# zeta2rework_lw_v20_wo_transistor.net
KiCad netlist of a schematic drawn in EAGLE
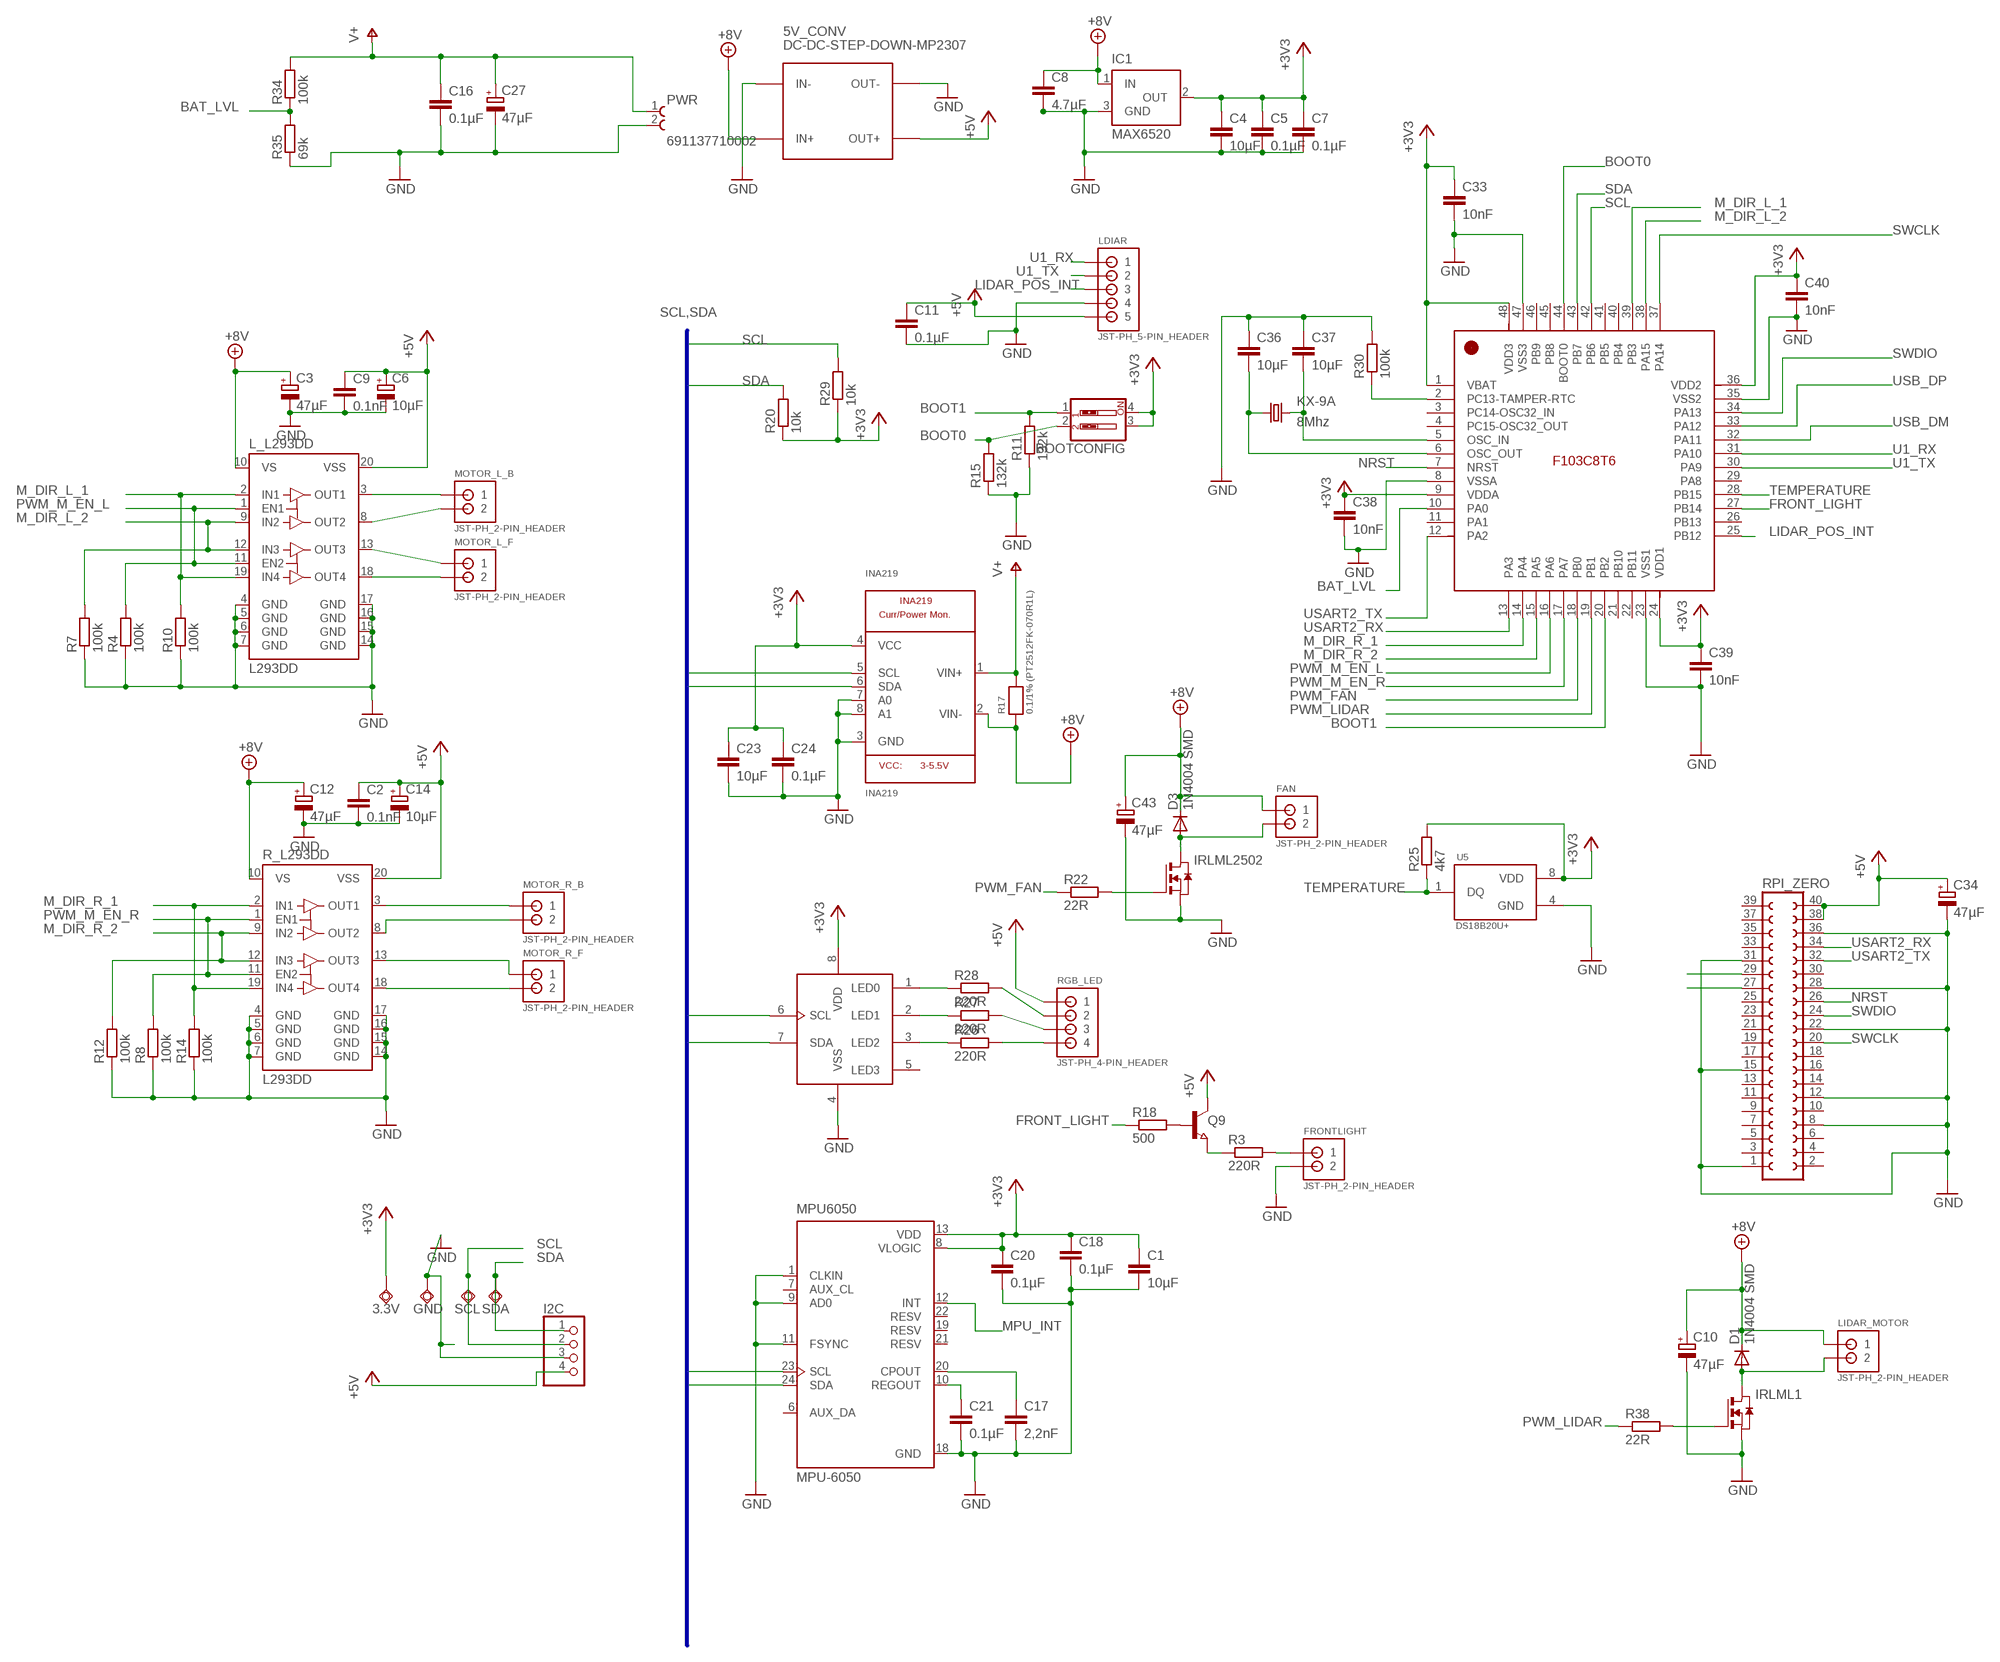
[diagram p0: schematic, sheet 1]

(export (version "E")
  (design (tool "Eeschema 10.0.6"))
  (components
    (comp (ref "3.3V")
      (value "TPSQTP20R")
      (footprint "eagle-import:TP20R")
      (libsource (lib "eagle-import") (part "TPSQTP20R"))
    )
    (comp (ref "5V_CONV")
      (value "DC-DC-STEP-DOWN-MP2307")
      (footprint "eagle-import:DC-DC-STEP-DOWN-MP2307")
      (libsource (lib "eagle-import") (part "DC-DC-STEP-DOWN-MP2307"))
    )
    (comp (ref "BOOTCONFIG")
      (value "SW_DIP-2")
      (footprint "eagle-import:EDG-02")
      (libsource (lib "eagle-import") (part "SW_DIP-2"))
    )
    (comp (ref "C1")
      (value "10µF")
      (footprint "eagle-import:C1206")
      (libsource (lib "eagle-import") (part "C-EUC1206"))
    )
    (comp (ref "C2")
      (value "0.1nF")
      (footprint "eagle-import:C1206")
      (libsource (lib "eagle-import") (part "C-EUC1206"))
    )
    (comp (ref "C3")
      (value "47µF")
      (footprint "eagle-import:UD-4X5,8_NICHICON")
      (libsource (lib "eagle-import") (part "CPOL-EUUD-4X5,8"))
    )
    (comp (ref "C4")
      (value "10µF")
      (footprint "eagle-import:C1206")
      (libsource (lib "eagle-import") (part "C-EUC1206"))
    )
    (comp (ref "C5")
      (value "0.1µF")
      (footprint "eagle-import:C1206")
      (libsource (lib "eagle-import") (part "C-EUC1206"))
    )
    (comp (ref "C6")
      (value "10µF")
      (footprint "eagle-import:UD-4X5,8_NICHICON")
      (libsource (lib "eagle-import") (part "CPOL-EUUD-4X5,8"))
    )
    (comp (ref "C7")
      (value "0.1µF")
      (footprint "eagle-import:C1206")
      (libsource (lib "eagle-import") (part "C-EUC1206"))
    )
    (comp (ref "C8")
      (value "4.7µF")
      (footprint "eagle-import:C1206")
      (libsource (lib "eagle-import") (part "C-EUC1206"))
    )
    (comp (ref "C9")
      (value "0.1nF")
      (footprint "eagle-import:C1206")
      (libsource (lib "eagle-import") (part "C-EUC1206"))
    )
    (comp (ref "C10")
      (value "47µF")
      (footprint "eagle-import:UD-4X5,8_NICHICON")
      (libsource (lib "eagle-import") (part "CPOL-EUUD-4X5,8"))
    )
    (comp (ref "C11")
      (value "0.1µF")
      (footprint "eagle-import:C1206")
      (libsource (lib "eagle-import") (part "C-EUC1206"))
    )
    (comp (ref "C12")
      (value "47µF")
      (footprint "eagle-import:UD-4X5,8_NICHICON")
      (libsource (lib "eagle-import") (part "CPOL-EUUD-4X5,8"))
    )
    (comp (ref "C14")
      (value "10µF")
      (footprint "eagle-import:UD-4X5,8_NICHICON")
      (libsource (lib "eagle-import") (part "CPOL-EUUD-4X5,8"))
    )
    (comp (ref "C16")
      (value "0.1µF")
      (footprint "eagle-import:C1206")
      (libsource (lib "eagle-import") (part "C-EUC1206"))
    )
    (comp (ref "C17")
      (value "2,2nF")
      (footprint "eagle-import:C1206")
      (libsource (lib "eagle-import") (part "C-EUC1206"))
    )
    (comp (ref "C18")
      (value "0.1µF")
      (footprint "eagle-import:C1206")
      (libsource (lib "eagle-import") (part "C-EUC1206"))
    )
    (comp (ref "C20")
      (value "0.1µF")
      (footprint "eagle-import:C1206")
      (libsource (lib "eagle-import") (part "C-EUC1206"))
    )
    (comp (ref "C21")
      (value "0.1µF")
      (footprint "eagle-import:C1206")
      (libsource (lib "eagle-import") (part "C-EUC1206"))
    )
    (comp (ref "C23")
      (value "10µF")
      (footprint "eagle-import:C1206")
      (libsource (lib "eagle-import") (part "C-EUC1206"))
    )
    (comp (ref "C24")
      (value "0.1µF")
      (footprint "eagle-import:C1206")
      (libsource (lib "eagle-import") (part "C-EUC1206"))
    )
    (comp (ref "C27")
      (value "47µF")
      (footprint "eagle-import:UD-4X5,8_NICHICON")
      (libsource (lib "eagle-import") (part "CPOL-EUUD-4X5,8"))
    )
    (comp (ref "C33")
      (value "10nF")
      (footprint "eagle-import:C1206")
      (libsource (lib "eagle-import") (part "C-EUC1206"))
    )
    (comp (ref "C34")
      (value "47µF")
      (footprint "eagle-import:UD-4X5,8_NICHICON")
      (libsource (lib "eagle-import") (part "CPOL-EUUD-4X5,8"))
    )
    (comp (ref "C36")
      (value "10µF")
      (footprint "eagle-import:C1206")
      (libsource (lib "eagle-import") (part "C-EUC1206"))
    )
    (comp (ref "C37")
      (value "10µF")
      (footprint "eagle-import:C1206")
      (libsource (lib "eagle-import") (part "C-EUC1206"))
    )
    (comp (ref "C38")
      (value "10nF")
      (footprint "eagle-import:C1206")
      (libsource (lib "eagle-import") (part "C-EUC1206"))
    )
    (comp (ref "C39")
      (value "10nF")
      (footprint "eagle-import:C1206")
      (libsource (lib "eagle-import") (part "C-EUC1206"))
    )
    (comp (ref "C40")
      (value "10nF")
      (footprint "eagle-import:C1206")
      (libsource (lib "eagle-import") (part "C-EUC1206"))
    )
    (comp (ref "C43")
      (value "47µF")
      (footprint "eagle-import:UD-4X5,8_NICHICON")
      (libsource (lib "eagle-import") (part "CPOL-EUUD-4X5,8"))
    )
    (comp (ref "D1")
      (value "1N4004 SMD")
      (footprint "eagle-import:DO214AC")
      (libsource (lib "eagle-import") (part "DIODE-DO214AC"))
    )
    (comp (ref "D3")
      (value "1N4004 SMD")
      (footprint "eagle-import:DO214AC")
      (libsource (lib "eagle-import") (part "DIODE-DO214AC"))
    )
    (comp (ref "FAN")
      (value "JST-PH_2-PIN_HEADER")
      (footprint "eagle-import:JST_B2B-PH_HEADER")
      (libsource (lib "eagle-import") (part "JST-PH_2-PIN_HEADER"))
    )
    (comp (ref "FRONTLIGHT")
      (value "JST-PH_2-PIN_HEADER")
      (footprint "eagle-import:JST_B2B-PH_HEADER")
      (libsource (lib "eagle-import") (part "JST-PH_2-PIN_HEADER"))
    )
    (comp (ref "GND")
      (value "TPSQTP20R")
      (footprint "eagle-import:TP20R")
      (libsource (lib "eagle-import") (part "TPSQTP20R"))
    )
    (comp (ref "I2C")
      (value "PINHD-1X4")
      (footprint "eagle-import:1X04")
      (libsource (lib "eagle-import") (part "PINHD-1X4"))
    )
    (comp (ref "IC1")
      (value "MAX6520")
      (footprint "eagle-import:SOT23")
      (fields (field (name "MF") "MAXIM") (field (name "MPN") "MAX6520EUR-T"))
      (libsource (lib "eagle-import") (part "MAX6520"))
    )
    (comp (ref "INA219")
      (value "INA219")
      (footprint "eagle-import:SOT23-8")
      (fields (field (name "MF") "Texas Instruments"))
      (libsource (lib "eagle-import") (part "INA219"))
    )
    (comp (ref "IRLML1")
      (value "NMOSSOT23")
      (footprint "eagle-import:SOT-23")
      (libsource (lib "eagle-import") (part "NMOSSOT23"))
    )
    (comp (ref "IRLML2502")
      (value "NMOSSOT23")
      (footprint "eagle-import:SOT-23")
      (libsource (lib "eagle-import") (part "NMOSSOT23"))
    )
    (comp (ref "KX-9A")
      (value "8Mhz")
      (footprint "eagle-import:5.0X3.2_KX-9A")
      (libsource (lib "eagle-import") (part "KX-9A"))
    )
    (comp (ref "LDIAR")
      (value "JST-PH_5-PIN_HEADER")
      (footprint "eagle-import:JST_B5B-PH_HEADER")
      (libsource (lib "eagle-import") (part "JST-PH_5-PIN_HEADER"))
    )
    (comp (ref "LIDAR_MOTOR")
      (value "JST-PH_2-PIN_HEADER")
      (footprint "eagle-import:JST_B2B-PH_HEADER")
      (libsource (lib "eagle-import") (part "JST-PH_2-PIN_HEADER"))
    )
    (comp (ref "L_L293DD")
      (value "L293DD")
      (footprint "eagle-import:SO20")
      (libsource (lib "eagle-import") (part "L293DD"))
    )
    (comp (ref "MOTOR_L_B")
      (value "JST-PH_2-PIN_HEADER")
      (footprint "eagle-import:JST_B2B-PH_HEADER")
      (libsource (lib "eagle-import") (part "JST-PH_2-PIN_HEADER"))
    )
    (comp (ref "MOTOR_L_F")
      (value "JST-PH_2-PIN_HEADER")
      (footprint "eagle-import:JST_B2B-PH_HEADER")
      (libsource (lib "eagle-import") (part "JST-PH_2-PIN_HEADER"))
    )
    (comp (ref "MOTOR_R_B")
      (value "JST-PH_2-PIN_HEADER")
      (footprint "eagle-import:JST_B2B-PH_HEADER")
      (libsource (lib "eagle-import") (part "JST-PH_2-PIN_HEADER"))
    )
    (comp (ref "MOTOR_R_F")
      (value "JST-PH_2-PIN_HEADER")
      (footprint "eagle-import:JST_B2B-PH_HEADER")
      (libsource (lib "eagle-import") (part "JST-PH_2-PIN_HEADER"))
    )
    (comp (ref "MPU6050")
      (value "MPU-6050")
      (footprint "eagle-import:QFN50P400X400X95-24N")
      (fields (field (name "MF") "TDK"))
      (libsource (lib "eagle-import") (part "MPU-6050"))
    )
    (comp (ref "PCA9533")
      (value "PCA9533")
      (footprint "eagle-import:SOIC8")
      (libsource (lib "eagle-import") (part "PCA9533"))
    )
    (comp (ref "PWR")
      (value "691137710002")
      (footprint "eagle-import:691137710002")
      (fields (field (name "MF") "Wurth Electronics"))
      (libsource (lib "eagle-import") (part "691137710002"))
    )
    (comp (ref "Q9")
      (value "NPN-TRANSISTOR_SOT23")
      (footprint "eagle-import:SOT23")
      (libsource (lib "eagle-import") (part "NPN-TRANSISTOR_SOT23"))
    )
    (comp (ref "R3")
      (value "220R")
      (footprint "eagle-import:R0603")
      (libsource (lib "eagle-import") (part "R-EU_R0603"))
    )
    (comp (ref "R4")
      (value "100k")
      (footprint "eagle-import:R0603")
      (libsource (lib "eagle-import") (part "R-EU_R0603"))
    )
    (comp (ref "R7")
      (value "100k")
      (footprint "eagle-import:R0603")
      (libsource (lib "eagle-import") (part "R-EU_R0603"))
    )
    (comp (ref "R8")
      (value "100k")
      (footprint "eagle-import:R0603")
      (libsource (lib "eagle-import") (part "R-EU_R0603"))
    )
    (comp (ref "R10")
      (value "100k")
      (footprint "eagle-import:R0603")
      (libsource (lib "eagle-import") (part "R-EU_R0603"))
    )
    (comp (ref "R11")
      (value "132k")
      (footprint "eagle-import:R0603")
      (libsource (lib "eagle-import") (part "R-EU_R0603"))
    )
    (comp (ref "R12")
      (value "100k")
      (footprint "eagle-import:R0603")
      (libsource (lib "eagle-import") (part "R-EU_R0603"))
    )
    (comp (ref "R14")
      (value "100k")
      (footprint "eagle-import:R0603")
      (libsource (lib "eagle-import") (part "R-EU_R0603"))
    )
    (comp (ref "R15")
      (value "132k")
      (footprint "eagle-import:R0603")
      (libsource (lib "eagle-import") (part "R-EU_R0603"))
    )
    (comp (ref "R17")
      (value "0.1/1% (PT2512FK-070R1L)")
      (footprint "eagle-import:2512")
      (libsource (lib "eagle-import") (part "RESISTOR2512"))
    )
    (comp (ref "R18")
      (value "500")
      (footprint "eagle-import:R0603")
      (libsource (lib "eagle-import") (part "R-EU_R0603"))
    )
    (comp (ref "R20")
      (value "10k")
      (footprint "eagle-import:R0603")
      (libsource (lib "eagle-import") (part "R-EU_R0603"))
    )
    (comp (ref "R22")
      (value "22R")
      (footprint "eagle-import:R0603")
      (libsource (lib "eagle-import") (part "R-EU_R0603"))
    )
    (comp (ref "R25")
      (value "4k7")
      (footprint "eagle-import:R0603")
      (libsource (lib "eagle-import") (part "R-EU_R0603"))
    )
    (comp (ref "R26")
      (value "220R")
      (footprint "eagle-import:R0603")
      (libsource (lib "eagle-import") (part "R-EU_R0603"))
    )
    (comp (ref "R27")
      (value "220R")
      (footprint "eagle-import:R0603")
      (libsource (lib "eagle-import") (part "R-EU_R0603"))
    )
    (comp (ref "R28")
      (value "220R")
      (footprint "eagle-import:R0603")
      (libsource (lib "eagle-import") (part "R-EU_R0603"))
    )
    (comp (ref "R29")
      (value "10k")
      (footprint "eagle-import:R0603")
      (libsource (lib "eagle-import") (part "R-EU_R0603"))
    )
    (comp (ref "R30")
      (value "100k")
      (footprint "eagle-import:R0603")
      (libsource (lib "eagle-import") (part "R-EU_R0603"))
    )
    (comp (ref "R34")
      (value "100k")
      (footprint "eagle-import:R0603")
      (libsource (lib "eagle-import") (part "R-EU_R0603"))
    )
    (comp (ref "R35")
      (value "69k")
      (footprint "eagle-import:R0603")
      (libsource (lib "eagle-import") (part "R-EU_R0603"))
    )
    (comp (ref "R38")
      (value "22R")
      (footprint "eagle-import:R0603")
      (libsource (lib "eagle-import") (part "R-EU_R0603"))
    )
    (comp (ref "RGB_LED")
      (value "JST-PH_4-PIN_HEADER")
      (footprint "eagle-import:JST_B4B-PH_HEADER")
      (libsource (lib "eagle-import") (part "JST-PH_4-PIN_HEADER"))
    )
    (comp (ref "RPI_ZERO")
      (value "FE20-2")
      (footprint "eagle-import:FE20-2")
      (libsource (lib "eagle-import") (part "FE20-2"))
    )
    (comp (ref "R_L293DD")
      (value "L293DD")
      (footprint "eagle-import:SO20")
      (libsource (lib "eagle-import") (part "L293DD"))
    )
    (comp (ref "SCL")
      (value "TPSQTP20R")
      (footprint "eagle-import:TP20R")
      (libsource (lib "eagle-import") (part "TPSQTP20R"))
    )
    (comp (ref "SDA")
      (value "TPSQTP20R")
      (footprint "eagle-import:TP20R")
      (libsource (lib "eagle-import") (part "TPSQTP20R"))
    )
    (comp (ref "STM32F103CB")
      (value "STM32F103CB")
      (footprint "eagle-import:LQFP48_7X7MM_0.5MMPP")
      (fields (field (name "MF") "STMicroelectronics") (field (name "MP") "STM32F103C8T6"))
      (libsource (lib "eagle-import") (part "STM32F103C8T6"))
    )
    (comp (ref "U5")
      (value "DS18B20U+")
      (footprint "eagle-import:SOP65P490X95-8N")
      (fields (field (name "MF") "Maxim"))
      (libsource (lib "eagle-import") (part "DS18B20U+"))
    )
  )
  (nets
    (net (code "1") (name "+3V3") (class "Default")
      (node (ref "3.3V") (pin "TP") (pinfunction "TP_TP") (pintype "input"))
      (node (ref "BOOTCONFIG") (pin "3") (pinfunction "3_3") (pintype "passive"))
      (node (ref "BOOTCONFIG") (pin "4") (pinfunction "4_4") (pintype "passive"))
      (node (ref "C1") (pin "1") (pinfunction "1_1") (pintype "passive"))
      (node (ref "C18") (pin "1") (pinfunction "1_1") (pintype "passive"))
      (node (ref "C20") (pin "1") (pinfunction "1_1") (pintype "passive"))
      (node (ref "C23") (pin "1") (pinfunction "1_1") (pintype "passive"))
      (node (ref "C24") (pin "1") (pinfunction "1_1") (pintype "passive"))
      (node (ref "C33") (pin "1") (pinfunction "1_1") (pintype "passive"))
      (node (ref "C38") (pin "1") (pinfunction "1_1") (pintype "passive"))
      (node (ref "C39") (pin "1") (pinfunction "1_1") (pintype "passive"))
      (node (ref "C4") (pin "1") (pinfunction "1_1") (pintype "passive"))
      (node (ref "C40") (pin "1") (pinfunction "1_1") (pintype "passive"))
      (node (ref "C5") (pin "1") (pinfunction "1_1") (pintype "passive"))
      (node (ref "C7") (pin "1") (pinfunction "1_1") (pintype "passive"))
      (node (ref "IC1") (pin "2") (pinfunction "OUT_2") (pintype "output"))
      (node (ref "INA219") (pin "4") (pinfunction "VCC_4") (pintype "bidirectional"))
      (node (ref "MPU6050") (pin "13") (pinfunction "VDD_13") (pintype "power_in"))
      (node (ref "MPU6050") (pin "8") (pinfunction "VLOGIC_8") (pintype "power_in"))
      (node (ref "PCA9533") (pin "8") (pinfunction "VDD_8") (pintype "power_in"))
      (node (ref "R20") (pin "1") (pinfunction "1_1") (pintype "passive"))
      (node (ref "R25") (pin "2") (pinfunction "2_2") (pintype "passive"))
      (node (ref "R29") (pin "1") (pinfunction "1_1") (pintype "passive"))
      (node (ref "STM32F103CB") (pin "1") (pinfunction "VBAT_1") (pintype "bidirectional"))
      (node (ref "STM32F103CB") (pin "24") (pinfunction "VDD1_24") (pintype "bidirectional"))
      (node (ref "STM32F103CB") (pin "36") (pinfunction "VDD2_36") (pintype "bidirectional"))
      (node (ref "STM32F103CB") (pin "48") (pinfunction "VDD3_48") (pintype "bidirectional"))
      (node (ref "STM32F103CB") (pin "9") (pinfunction "VDDA_9") (pintype "bidirectional"))
      (node (ref "U5") (pin "8") (pinfunction "VDD_8") (pintype "power_in"))
    )
    (net (code "2") (name "+5V") (class "Default")
      (node (ref "5V_CONV") (pin "OUT+") (pinfunction "OUT+_OUT+") (pintype "bidirectional"))
      (node (ref "C11") (pin "1") (pinfunction "1_1") (pintype "passive"))
      (node (ref "C14") (pin "+") (pinfunction "+_+") (pintype "passive"))
      (node (ref "C2") (pin "1") (pinfunction "1_1") (pintype "passive"))
      (node (ref "C34") (pin "+") (pinfunction "+_+") (pintype "passive"))
      (node (ref "C6") (pin "+") (pinfunction "+_+") (pintype "passive"))
      (node (ref "C9") (pin "1") (pinfunction "1_1") (pintype "passive"))
      (node (ref "I2C") (pin "4") (pinfunction "4_4") (pintype "passive"))
      (node (ref "LDIAR") (pin "P5") (pinfunction "5_P5") (pintype "bidirectional"))
      (node (ref "L_L293DD") (pin "20") (pinfunction "VSS_20") (pintype "power_in"))
      (node (ref "Q9") (pin "3") (pinfunction "C_3") (pintype "passive"))
      (node (ref "RGB_LED") (pin "P1") (pinfunction "1_P1") (pintype "bidirectional"))
      (node (ref "RPI_ZERO") (pin "38") (pinfunction "38_38") (pintype "passive"))
      (node (ref "RPI_ZERO") (pin "40") (pinfunction "40_40") (pintype "passive"))
      (node (ref "R_L293DD") (pin "20") (pinfunction "VSS_20") (pintype "power_in"))
    )
    (net (code "3") (name "+8V") (class "Default")
      (node (ref "5V_CONV") (pin "IN+") (pinfunction "IN+_IN+") (pintype "bidirectional"))
      (node (ref "C10") (pin "+") (pinfunction "+_+") (pintype "passive"))
      (node (ref "C12") (pin "+") (pinfunction "+_+") (pintype "passive"))
      (node (ref "C3") (pin "+") (pinfunction "+_+") (pintype "passive"))
      (node (ref "C43") (pin "+") (pinfunction "+_+") (pintype "passive"))
      (node (ref "C8") (pin "1") (pinfunction "1_1") (pintype "passive"))
      (node (ref "D1") (pin "C") (pinfunction "C_C") (pintype "passive"))
      (node (ref "D3") (pin "C") (pinfunction "C_C") (pintype "passive"))
      (node (ref "FAN") (pin "P1") (pinfunction "1_P1") (pintype "bidirectional"))
      (node (ref "IC1") (pin "1") (pinfunction "IN_1") (pintype "input"))
      (node (ref "INA219") (pin "2") (pinfunction "VIN-_2") (pintype "bidirectional"))
      (node (ref "LIDAR_MOTOR") (pin "P1") (pinfunction "1_P1") (pintype "bidirectional"))
      (node (ref "L_L293DD") (pin "10") (pinfunction "VS_10") (pintype "power_in"))
      (node (ref "R17") (pin "1") (pinfunction "1_1") (pintype "passive"))
      (node (ref "R_L293DD") (pin "10") (pinfunction "VS_10") (pintype "power_in"))
    )
    (net (code "4") (name "/BAT_LVL") (class "Default")
      (node (ref "R34") (pin "1") (pinfunction "1_1") (pintype "passive"))
      (node (ref "R35") (pin "2") (pinfunction "2_2") (pintype "passive"))
      (node (ref "STM32F103CB") (pin "10") (pinfunction "PA0_10") (pintype "bidirectional"))
    )
    (net (code "5") (name "/BOOT0") (class "Default")
      (node (ref "BOOTCONFIG") (pin "2") (pinfunction "2_2") (pintype "passive"))
      (node (ref "R15") (pin "2") (pinfunction "2_2") (pintype "passive"))
      (node (ref "STM32F103CB") (pin "44") (pinfunction "BOOT0_44") (pintype "bidirectional"))
    )
    (net (code "6") (name "/BOOT1") (class "Default")
      (node (ref "BOOTCONFIG") (pin "1") (pinfunction "1_1") (pintype "passive"))
      (node (ref "R11") (pin "2") (pinfunction "2_2") (pintype "passive"))
      (node (ref "STM32F103CB") (pin "20") (pinfunction "PB2_20") (pintype "bidirectional"))
    )
    (net (code "7") (name "/FRONT_LIGHT") (class "Default")
      (node (ref "R18") (pin "1") (pinfunction "1_1") (pintype "passive"))
      (node (ref "STM32F103CB") (pin "27") (pinfunction "PB14_27") (pintype "bidirectional"))
    )
    (net (code "8") (name "/LIDAR_POS_INT") (class "Default")
      (node (ref "LDIAR") (pin "P3") (pinfunction "3_P3") (pintype "bidirectional"))
      (node (ref "STM32F103CB") (pin "25") (pinfunction "PB12_25") (pintype "bidirectional"))
    )
    (net (code "9") (name "/MPU_INT") (class "Default")
      (node (ref "MPU6050") (pin "12") (pinfunction "INT_12") (pintype "output"))
    )
    (net (code "10") (name "/M_DIR_L_1") (class "Default")
      (node (ref "L_L293DD") (pin "19") (pinfunction "IN4_19") (pintype "input"))
      (node (ref "L_L293DD") (pin "2") (pinfunction "IN1_2") (pintype "input"))
      (node (ref "R10") (pin "2") (pinfunction "2_2") (pintype "passive"))
      (node (ref "STM32F103CB") (pin "39") (pinfunction "PB3_39") (pintype "bidirectional"))
    )
    (net (code "11") (name "/M_DIR_L_2") (class "Default")
      (node (ref "L_L293DD") (pin "12") (pinfunction "IN3_12") (pintype "input"))
      (node (ref "L_L293DD") (pin "9") (pinfunction "IN2_9") (pintype "input"))
      (node (ref "R7") (pin "2") (pinfunction "2_2") (pintype "passive"))
      (node (ref "STM32F103CB") (pin "38") (pinfunction "PA15_38") (pintype "bidirectional"))
    )
    (net (code "12") (name "/M_DIR_R_1") (class "Default")
      (node (ref "R14") (pin "2") (pinfunction "2_2") (pintype "passive"))
      (node (ref "R_L293DD") (pin "19") (pinfunction "IN4_19") (pintype "input"))
      (node (ref "R_L293DD") (pin "2") (pinfunction "IN1_2") (pintype "input"))
      (node (ref "STM32F103CB") (pin "14") (pinfunction "PA4_14") (pintype "bidirectional"))
    )
    (net (code "13") (name "/M_DIR_R_2") (class "Default")
      (node (ref "R12") (pin "2") (pinfunction "2_2") (pintype "passive"))
      (node (ref "R_L293DD") (pin "12") (pinfunction "IN3_12") (pintype "input"))
      (node (ref "R_L293DD") (pin "9") (pinfunction "IN2_9") (pintype "input"))
      (node (ref "STM32F103CB") (pin "15") (pinfunction "PA5_15") (pintype "bidirectional"))
    )
    (net (code "14") (name "/NRST") (class "Default")
      (node (ref "RPI_ZERO") (pin "26") (pinfunction "26_26") (pintype "passive"))
      (node (ref "STM32F103CB") (pin "7") (pinfunction "NRST_7") (pintype "bidirectional"))
    )
    (net (code "15") (name "/PWM_FAN") (class "Default")
      (node (ref "R22") (pin "1") (pinfunction "1_1") (pintype "passive"))
      (node (ref "STM32F103CB") (pin "18") (pinfunction "PB0_18") (pintype "bidirectional"))
    )
    (net (code "16") (name "/PWM_LIDAR") (class "Default")
      (node (ref "R38") (pin "1") (pinfunction "1_1") (pintype "passive"))
      (node (ref "STM32F103CB") (pin "19") (pinfunction "PB1_19") (pintype "bidirectional"))
    )
    (net (code "17") (name "/PWM_M_EN_L") (class "Default")
      (node (ref "L_L293DD") (pin "1") (pinfunction "EN1_1") (pintype "input"))
      (node (ref "L_L293DD") (pin "11") (pinfunction "EN2_11") (pintype "input"))
      (node (ref "R4") (pin "2") (pinfunction "2_2") (pintype "passive"))
      (node (ref "STM32F103CB") (pin "16") (pinfunction "PA6_16") (pintype "bidirectional"))
    )
    (net (code "18") (name "/PWM_M_EN_R") (class "Default")
      (node (ref "R8") (pin "2") (pinfunction "2_2") (pintype "passive"))
      (node (ref "R_L293DD") (pin "1") (pinfunction "EN1_1") (pintype "input"))
      (node (ref "R_L293DD") (pin "11") (pinfunction "EN2_11") (pintype "input"))
      (node (ref "STM32F103CB") (pin "17") (pinfunction "PA7_17") (pintype "bidirectional"))
    )
    (net (code "19") (name "/SCL") (class "Default")
      (node (ref "I2C") (pin "2") (pinfunction "2_2") (pintype "passive"))
      (node (ref "INA219") (pin "5") (pinfunction "SCL_5") (pintype "bidirectional"))
      (node (ref "MPU6050") (pin "23") (pinfunction "SCL_23") (pintype "input"))
      (node (ref "PCA9533") (pin "6") (pinfunction "SCL_6") (pintype "input"))
      (node (ref "R29") (pin "2") (pinfunction "2_2") (pintype "passive"))
      (node (ref "SCL") (pin "TP") (pinfunction "TP_TP") (pintype "input"))
      (node (ref "STM32F103CB") (pin "42") (pinfunction "PB6_42") (pintype "bidirectional"))
    )
    (net (code "20") (name "/SDA") (class "Default")
      (node (ref "I2C") (pin "1") (pinfunction "1_1") (pintype "passive"))
      (node (ref "INA219") (pin "6") (pinfunction "SDA_6") (pintype "bidirectional"))
      (node (ref "MPU6050") (pin "24") (pinfunction "SDA_24") (pintype "bidirectional"))
      (node (ref "PCA9533") (pin "7") (pinfunction "SDA_7") (pintype "bidirectional"))
      (node (ref "R20") (pin "2") (pinfunction "2_2") (pintype "passive"))
      (node (ref "SDA") (pin "TP") (pinfunction "TP_TP") (pintype "input"))
      (node (ref "STM32F103CB") (pin "43") (pinfunction "PB7_43") (pintype "bidirectional"))
    )
    (net (code "21") (name "/SWCLK") (class "Default")
      (node (ref "RPI_ZERO") (pin "20") (pinfunction "20_20") (pintype "passive"))
      (node (ref "STM32F103CB") (pin "37") (pinfunction "PA14_37") (pintype "bidirectional"))
    )
    (net (code "22") (name "/SWDIO") (class "Default")
      (node (ref "RPI_ZERO") (pin "24") (pinfunction "24_24") (pintype "passive"))
      (node (ref "STM32F103CB") (pin "34") (pinfunction "PA13_34") (pintype "bidirectional"))
    )
    (net (code "23") (name "/TEMPERATURE") (class "Default")
      (node (ref "R25") (pin "1") (pinfunction "1_1") (pintype "passive"))
      (node (ref "STM32F103CB") (pin "28") (pinfunction "PB15_28") (pintype "bidirectional"))
      (node (ref "U5") (pin "1") (pinfunction "DQ_1") (pintype "bidirectional"))
    )
    (net (code "24") (name "/U1_RX") (class "Default")
      (node (ref "LDIAR") (pin "P1") (pinfunction "1_P1") (pintype "bidirectional"))
      (node (ref "STM32F103CB") (pin "31") (pinfunction "PA10_31") (pintype "bidirectional"))
    )
    (net (code "25") (name "/U1_TX") (class "Default")
      (node (ref "LDIAR") (pin "P2") (pinfunction "2_P2") (pintype "bidirectional"))
      (node (ref "STM32F103CB") (pin "30") (pinfunction "PA9_30") (pintype "bidirectional"))
    )
    (net (code "26") (name "/USART2_RX") (class "Default")
      (node (ref "RPI_ZERO") (pin "34") (pinfunction "34_34") (pintype "passive"))
      (node (ref "STM32F103CB") (pin "13") (pinfunction "PA3_13") (pintype "bidirectional"))
    )
    (net (code "27") (name "/USART2_TX") (class "Default")
      (node (ref "RPI_ZERO") (pin "32") (pinfunction "32_32") (pintype "passive"))
      (node (ref "STM32F103CB") (pin "12") (pinfunction "PA2_12") (pintype "bidirectional"))
    )
    (net (code "28") (name "/USB_DM") (class "Default")
      (node (ref "STM32F103CB") (pin "32") (pinfunction "PA11_32") (pintype "bidirectional"))
    )
    (net (code "29") (name "/USB_DP") (class "Default")
      (node (ref "STM32F103CB") (pin "33") (pinfunction "PA12_33") (pintype "bidirectional"))
    )
    (net (code "31") (name "GND") (class "Default")
      (node (ref "5V_CONV") (pin "IN-") (pinfunction "IN-_IN-") (pintype "bidirectional"))
      (node (ref "5V_CONV") (pin "OUT-") (pinfunction "OUT-_OUT-") (pintype "bidirectional"))
      (node (ref "C1") (pin "2") (pinfunction "2_2") (pintype "passive"))
      (node (ref "C10") (pin "-") (pinfunction "-_-") (pintype "passive"))
      (node (ref "C11") (pin "2") (pinfunction "2_2") (pintype "passive"))
      (node (ref "C12") (pin "-") (pinfunction "-_-") (pintype "passive"))
      (node (ref "C14") (pin "-") (pinfunction "-_-") (pintype "passive"))
      (node (ref "C16") (pin "2") (pinfunction "2_2") (pintype "passive"))
      (node (ref "C17") (pin "2") (pinfunction "2_2") (pintype "passive"))
      (node (ref "C18") (pin "2") (pinfunction "2_2") (pintype "passive"))
      (node (ref "C2") (pin "2") (pinfunction "2_2") (pintype "passive"))
      (node (ref "C20") (pin "2") (pinfunction "2_2") (pintype "passive"))
      (node (ref "C21") (pin "2") (pinfunction "2_2") (pintype "passive"))
      (node (ref "C23") (pin "2") (pinfunction "2_2") (pintype "passive"))
      (node (ref "C24") (pin "2") (pinfunction "2_2") (pintype "passive"))
      (node (ref "C27") (pin "-") (pinfunction "-_-") (pintype "passive"))
      (node (ref "C3") (pin "-") (pinfunction "-_-") (pintype "passive"))
      (node (ref "C33") (pin "2") (pinfunction "2_2") (pintype "passive"))
      (node (ref "C34") (pin "-") (pinfunction "-_-") (pintype "passive"))
      (node (ref "C36") (pin "1") (pinfunction "1_1") (pintype "passive"))
      (node (ref "C37") (pin "1") (pinfunction "1_1") (pintype "passive"))
      (node (ref "C38") (pin "2") (pinfunction "2_2") (pintype "passive"))
      (node (ref "C39") (pin "2") (pinfunction "2_2") (pintype "passive"))
      (node (ref "C4") (pin "2") (pinfunction "2_2") (pintype "passive"))
      (node (ref "C40") (pin "2") (pinfunction "2_2") (pintype "passive"))
      (node (ref "C43") (pin "-") (pinfunction "-_-") (pintype "passive"))
      (node (ref "C5") (pin "2") (pinfunction "2_2") (pintype "passive"))
      (node (ref "C6") (pin "-") (pinfunction "-_-") (pintype "passive"))
      (node (ref "C7") (pin "2") (pinfunction "2_2") (pintype "passive"))
      (node (ref "C8") (pin "2") (pinfunction "2_2") (pintype "passive"))
      (node (ref "C9") (pin "2") (pinfunction "2_2") (pintype "passive"))
      (node (ref "FRONTLIGHT") (pin "P2") (pinfunction "2_P2") (pintype "bidirectional"))
      (node (ref "GND") (pin "TP") (pinfunction "TP_TP") (pintype "input"))
      (node (ref "I2C") (pin "3") (pinfunction "3_3") (pintype "passive"))
      (node (ref "IC1") (pin "3") (pinfunction "GND_3") (pintype "power_in"))
      (node (ref "INA219") (pin "3") (pinfunction "GND_3") (pintype "bidirectional"))
      (node (ref "INA219") (pin "7") (pinfunction "A0_7") (pintype "bidirectional"))
      (node (ref "INA219") (pin "8") (pinfunction "A1_8") (pintype "bidirectional"))
      (node (ref "IRLML1") (pin "2") (pinfunction "S_2") (pintype "passive"))
      (node (ref "IRLML2502") (pin "2") (pinfunction "S_2") (pintype "passive"))
      (node (ref "LDIAR") (pin "P4") (pinfunction "4_P4") (pintype "bidirectional"))
      (node (ref "L_L293DD") (pin "14") (pinfunction "GND_14") (pintype "power_in"))
      (node (ref "L_L293DD") (pin "15") (pinfunction "GND_15") (pintype "power_in"))
      (node (ref "L_L293DD") (pin "16") (pinfunction "GND_16") (pintype "power_in"))
      (node (ref "L_L293DD") (pin "17") (pinfunction "GND_17") (pintype "power_in"))
      (node (ref "L_L293DD") (pin "4") (pinfunction "GND_4") (pintype "power_in"))
      (node (ref "L_L293DD") (pin "5") (pinfunction "GND_5") (pintype "power_in"))
      (node (ref "L_L293DD") (pin "6") (pinfunction "GND_6") (pintype "power_in"))
      (node (ref "L_L293DD") (pin "7") (pinfunction "GND_7") (pintype "power_in"))
      (node (ref "MPU6050") (pin "1") (pinfunction "CLKIN_1") (pintype "input"))
      (node (ref "MPU6050") (pin "11") (pinfunction "FSYNC_11") (pintype "input"))
      (node (ref "MPU6050") (pin "18") (pinfunction "GND_18") (pintype "power_in"))
      (node (ref "MPU6050") (pin "9") (pinfunction "AD0_9") (pintype "input"))
      (node (ref "PCA9533") (pin "4") (pinfunction "VSS_4") (pintype "power_in"))
      (node (ref "PWR") (pin "2") (pinfunction "2_2") (pintype "passive"))
      (node (ref "R10") (pin "1") (pinfunction "1_1") (pintype "passive"))
      (node (ref "R11") (pin "1") (pinfunction "1_1") (pintype "passive"))
      (node (ref "R12") (pin "1") (pinfunction "1_1") (pintype "passive"))
      (node (ref "R14") (pin "1") (pinfunction "1_1") (pintype "passive"))
      (node (ref "R15") (pin "1") (pinfunction "1_1") (pintype "passive"))
      (node (ref "R30") (pin "2") (pinfunction "2_2") (pintype "passive"))
      (node (ref "R35") (pin "1") (pinfunction "1_1") (pintype "passive"))
      (node (ref "R4") (pin "1") (pinfunction "1_1") (pintype "passive"))
      (node (ref "R7") (pin "1") (pinfunction "1_1") (pintype "passive"))
      (node (ref "R8") (pin "1") (pinfunction "1_1") (pintype "passive"))
      (node (ref "RPI_ZERO") (pin "1") (pinfunction "1_1") (pintype "passive"))
      (node (ref "RPI_ZERO") (pin "12") (pinfunction "12_12") (pintype "passive"))
      (node (ref "RPI_ZERO") (pin "15") (pinfunction "15_15") (pintype "passive"))
      (node (ref "RPI_ZERO") (pin "22") (pinfunction "22_22") (pintype "passive"))
      (node (ref "RPI_ZERO") (pin "28") (pinfunction "28_28") (pintype "passive"))
      (node (ref "RPI_ZERO") (pin "31") (pinfunction "31_31") (pintype "passive"))
      (node (ref "RPI_ZERO") (pin "36") (pinfunction "36_36") (pintype "passive"))
      (node (ref "RPI_ZERO") (pin "8") (pinfunction "8_8") (pintype "passive"))
      (node (ref "R_L293DD") (pin "14") (pinfunction "GND_14") (pintype "power_in"))
      (node (ref "R_L293DD") (pin "15") (pinfunction "GND_15") (pintype "power_in"))
      (node (ref "R_L293DD") (pin "16") (pinfunction "GND_16") (pintype "power_in"))
      (node (ref "R_L293DD") (pin "17") (pinfunction "GND_17") (pintype "power_in"))
      (node (ref "R_L293DD") (pin "4") (pinfunction "GND_4") (pintype "power_in"))
      (node (ref "R_L293DD") (pin "5") (pinfunction "GND_5") (pintype "power_in"))
      (node (ref "R_L293DD") (pin "6") (pinfunction "GND_6") (pintype "power_in"))
      (node (ref "R_L293DD") (pin "7") (pinfunction "GND_7") (pintype "power_in"))
      (node (ref "STM32F103CB") (pin "23") (pinfunction "VSS1_23") (pintype "bidirectional"))
      (node (ref "STM32F103CB") (pin "35") (pinfunction "VSS2_35") (pintype "bidirectional"))
      (node (ref "STM32F103CB") (pin "47") (pinfunction "VSS3_47") (pintype "bidirectional"))
      (node (ref "STM32F103CB") (pin "8") (pinfunction "VSSA_8") (pintype "bidirectional"))
      (node (ref "U5") (pin "4") (pinfunction "GND_4") (pintype "power_in"))
    )
    (net (code "32") (name "Net-(FAN-2)") (class "Default")
      (node (ref "D3") (pin "A") (pinfunction "A_A") (pintype "passive"))
      (node (ref "FAN") (pin "P2") (pinfunction "2_P2") (pintype "bidirectional"))
      (node (ref "IRLML2502") (pin "1") (pinfunction "D_1") (pintype "passive"))
    )
    (net (code "33") (name "Net-(FRONTLIGHT-1)") (class "Default")
      (node (ref "FRONTLIGHT") (pin "P1") (pinfunction "1_P1") (pintype "bidirectional"))
      (node (ref "R3") (pin "2") (pinfunction "2_2") (pintype "passive"))
    )
    (net (code "34") (name "Net-(IRLML1-D)") (class "Default")
      (node (ref "D1") (pin "A") (pinfunction "A_A") (pintype "passive"))
      (node (ref "IRLML1") (pin "1") (pinfunction "D_1") (pintype "passive"))
      (node (ref "LIDAR_MOTOR") (pin "P2") (pinfunction "2_P2") (pintype "bidirectional"))
    )
    (net (code "35") (name "Net-(IRLML1-G)") (class "Default")
      (node (ref "IRLML1") (pin "3") (pinfunction "G_3") (pintype "passive"))
      (node (ref "R38") (pin "2") (pinfunction "2_2") (pintype "passive"))
    )
    (net (code "36") (name "Net-(IRLML2502-G)") (class "Default")
      (node (ref "IRLML2502") (pin "3") (pinfunction "G_3") (pintype "passive"))
      (node (ref "R22") (pin "2") (pinfunction "2_2") (pintype "passive"))
    )
    (net (code "37") (name "Net-(KX-9A-2)") (class "Default")
      (node (ref "C37") (pin "2") (pinfunction "2_2") (pintype "passive"))
      (node (ref "KX-9A") (pin "3") (pinfunction "2_3") (pintype "passive"))
      (node (ref "STM32F103CB") (pin "5") (pinfunction "OSC_IN_5") (pintype "bidirectional"))
    )
    (net (code "38") (name "Net-(L_L293DD-OUT1)") (class "Default")
      (node (ref "L_L293DD") (pin "3") (pinfunction "OUT1_3") (pintype "output"))
      (node (ref "MOTOR_L_B") (pin "P1") (pinfunction "1_P1") (pintype "bidirectional"))
    )
    (net (code "39") (name "Net-(L_L293DD-OUT2)") (class "Default")
      (node (ref "L_L293DD") (pin "8") (pinfunction "OUT2_8") (pintype "output"))
      (node (ref "MOTOR_L_B") (pin "P2") (pinfunction "2_P2") (pintype "bidirectional"))
    )
    (net (code "40") (name "Net-(L_L293DD-OUT3)") (class "Default")
      (node (ref "L_L293DD") (pin "13") (pinfunction "OUT3_13") (pintype "output"))
      (node (ref "MOTOR_L_F") (pin "P1") (pinfunction "1_P1") (pintype "bidirectional"))
    )
    (net (code "41") (name "Net-(L_L293DD-OUT4)") (class "Default")
      (node (ref "L_L293DD") (pin "18") (pinfunction "OUT4_18") (pintype "output"))
      (node (ref "MOTOR_L_F") (pin "P2") (pinfunction "2_P2") (pintype "bidirectional"))
    )
    (net (code "42") (name "Net-(MOTOR_R_B-1)") (class "Default")
      (node (ref "MOTOR_R_B") (pin "P1") (pinfunction "1_P1") (pintype "bidirectional"))
      (node (ref "R_L293DD") (pin "3") (pinfunction "OUT1_3") (pintype "output"))
    )
    (net (code "43") (name "Net-(MOTOR_R_B-2)") (class "Default")
      (node (ref "MOTOR_R_B") (pin "P2") (pinfunction "2_P2") (pintype "bidirectional"))
      (node (ref "R_L293DD") (pin "8") (pinfunction "OUT2_8") (pintype "output"))
    )
    (net (code "44") (name "Net-(MOTOR_R_F-1)") (class "Default")
      (node (ref "MOTOR_R_F") (pin "P1") (pinfunction "1_P1") (pintype "bidirectional"))
      (node (ref "R_L293DD") (pin "13") (pinfunction "OUT3_13") (pintype "output"))
    )
    (net (code "45") (name "Net-(MOTOR_R_F-2)") (class "Default")
      (node (ref "MOTOR_R_F") (pin "P2") (pinfunction "2_P2") (pintype "bidirectional"))
      (node (ref "R_L293DD") (pin "18") (pinfunction "OUT4_18") (pintype "output"))
    )
    (net (code "46") (name "Net-(MPU6050-CPOUT)") (class "Default")
      (node (ref "C17") (pin "1") (pinfunction "1_1") (pintype "passive"))
      (node (ref "MPU6050") (pin "20") (pinfunction "CPOUT_20") (pintype "passive"))
    )
    (net (code "47") (name "Net-(MPU6050-REGOUT)") (class "Default")
      (node (ref "C21") (pin "1") (pinfunction "1_1") (pintype "passive"))
      (node (ref "MPU6050") (pin "10") (pinfunction "REGOUT_10") (pintype "passive"))
    )
    (net (code "48") (name "Net-(PCA9533-LED0)") (class "Default")
      (node (ref "PCA9533") (pin "1") (pinfunction "LED0_1") (pintype "bidirectional"))
      (node (ref "R28") (pin "1") (pinfunction "1_1") (pintype "passive"))
    )
    (net (code "49") (name "Net-(PCA9533-LED1)") (class "Default")
      (node (ref "PCA9533") (pin "2") (pinfunction "LED1_2") (pintype "bidirectional"))
      (node (ref "R27") (pin "1") (pinfunction "1_1") (pintype "passive"))
    )
    (net (code "50") (name "Net-(PCA9533-LED2)") (class "Default")
      (node (ref "PCA9533") (pin "3") (pinfunction "LED2_3") (pintype "bidirectional"))
      (node (ref "R26") (pin "1") (pinfunction "1_1") (pintype "passive"))
    )
    (net (code "51") (name "Net-(Q9-B)") (class "Default")
      (node (ref "Q9") (pin "1") (pinfunction "B_1") (pintype "passive"))
      (node (ref "R18") (pin "2") (pinfunction "2_2") (pintype "passive"))
    )
    (net (code "52") (name "Net-(Q9-E)") (class "Default")
      (node (ref "Q9") (pin "2") (pinfunction "E_2") (pintype "passive"))
      (node (ref "R3") (pin "1") (pinfunction "1_1") (pintype "passive"))
    )
    (net (code "53") (name "Net-(RGB_LED-2)") (class "Default")
      (node (ref "R28") (pin "2") (pinfunction "2_2") (pintype "passive"))
      (node (ref "RGB_LED") (pin "P2") (pinfunction "2_P2") (pintype "bidirectional"))
    )
    (net (code "54") (name "Net-(RGB_LED-3)") (class "Default")
      (node (ref "R27") (pin "2") (pinfunction "2_2") (pintype "passive"))
      (node (ref "RGB_LED") (pin "P3") (pinfunction "3_P3") (pintype "bidirectional"))
    )
    (net (code "55") (name "Net-(RGB_LED-4)") (class "Default")
      (node (ref "R26") (pin "2") (pinfunction "2_2") (pintype "passive"))
      (node (ref "RGB_LED") (pin "P4") (pinfunction "4_P4") (pintype "bidirectional"))
    )
    (net (code "56") (name "Net-(STM32F103CB-OSC_OUT)") (class "Default")
      (node (ref "C36") (pin "2") (pinfunction "2_2") (pintype "passive"))
      (node (ref "KX-9A") (pin "1") (pinfunction "1_1") (pintype "passive"))
      (node (ref "STM32F103CB") (pin "6") (pinfunction "OSC_OUT_6") (pintype "bidirectional"))
    )
    (net (code "57") (name "Net-(STM32F103CB-PC13-TAMPER-RTC)") (class "Default")
      (node (ref "R30") (pin "1") (pinfunction "1_1") (pintype "passive"))
      (node (ref "STM32F103CB") (pin "2") (pinfunction "PC13-TAMPER-RTC_2") (pintype "bidirectional"))
    )
    (net (code "58") (name "V+") (class "Default")
      (node (ref "C16") (pin "1") (pinfunction "1_1") (pintype "passive"))
      (node (ref "C27") (pin "+") (pinfunction "+_+") (pintype "passive"))
      (node (ref "INA219") (pin "1") (pinfunction "VIN+_1") (pintype "bidirectional"))
      (node (ref "PWR") (pin "1") (pinfunction "1_1") (pintype "passive"))
      (node (ref "R17") (pin "2") (pinfunction "2_2") (pintype "passive"))
      (node (ref "R34") (pin "2") (pinfunction "2_2") (pintype "passive"))
    )
    (net (code "59") (name "unconnected-(MPU6050-AUX_CL-Pad7)") (class "Default")
      (node (ref "MPU6050") (pin "7") (pinfunction "AUX_CL_7") (pintype "input"))
    )
    (net (code "60") (name "unconnected-(MPU6050-AUX_DA-Pad6)") (class "Default")
      (node (ref "MPU6050") (pin "6") (pinfunction "AUX_DA_6") (pintype "bidirectional"))
    )
    (net (code "61") (name "unconnected-(MPU6050-RESV-Pad19)") (class "Default")
      (node (ref "MPU6050") (pin "19") (pinfunction "RESV_19") (pintype "passive"))
    )
    (net (code "62") (name "unconnected-(MPU6050-RESV-Pad21)") (class "Default")
      (node (ref "MPU6050") (pin "21") (pinfunction "RESV_21") (pintype "passive"))
    )
    (net (code "63") (name "unconnected-(MPU6050-RESV-Pad22)") (class "Default")
      (node (ref "MPU6050") (pin "22") (pinfunction "RESV_22") (pintype "passive"))
    )
    (net (code "64") (name "unconnected-(PCA9533-LED3-Pad5)") (class "Default")
      (node (ref "PCA9533") (pin "5") (pinfunction "LED3_5") (pintype "bidirectional"))
    )
    (net (code "65") (name "unconnected-(RPI_ZERO-Pad2)") (class "Default")
      (node (ref "RPI_ZERO") (pin "2") (pinfunction "2_2") (pintype "passive"))
    )
    (net (code "66") (name "unconnected-(RPI_ZERO-Pad3)") (class "Default")
      (node (ref "RPI_ZERO") (pin "3") (pinfunction "3_3") (pintype "passive"))
    )
    (net (code "67") (name "unconnected-(RPI_ZERO-Pad4)") (class "Default")
      (node (ref "RPI_ZERO") (pin "4") (pinfunction "4_4") (pintype "passive"))
    )
    (net (code "68") (name "unconnected-(RPI_ZERO-Pad5)") (class "Default")
      (node (ref "RPI_ZERO") (pin "5") (pinfunction "5_5") (pintype "passive"))
    )
    (net (code "69") (name "unconnected-(RPI_ZERO-Pad6)") (class "Default")
      (node (ref "RPI_ZERO") (pin "6") (pinfunction "6_6") (pintype "passive"))
    )
    (net (code "70") (name "unconnected-(RPI_ZERO-Pad7)") (class "Default")
      (node (ref "RPI_ZERO") (pin "7") (pinfunction "7_7") (pintype "passive"))
    )
    (net (code "71") (name "unconnected-(RPI_ZERO-Pad9)") (class "Default")
      (node (ref "RPI_ZERO") (pin "9") (pinfunction "9_9") (pintype "passive"))
    )
    (net (code "72") (name "unconnected-(RPI_ZERO-Pad10)") (class "Default")
      (node (ref "RPI_ZERO") (pin "10") (pinfunction "10_10") (pintype "passive"))
    )
    (net (code "73") (name "unconnected-(RPI_ZERO-Pad11)") (class "Default")
      (node (ref "RPI_ZERO") (pin "11") (pinfunction "11_11") (pintype "passive"))
    )
    (net (code "74") (name "unconnected-(RPI_ZERO-Pad13)") (class "Default")
      (node (ref "RPI_ZERO") (pin "13") (pinfunction "13_13") (pintype "passive"))
    )
    (net (code "75") (name "unconnected-(RPI_ZERO-Pad14)") (class "Default")
      (node (ref "RPI_ZERO") (pin "14") (pinfunction "14_14") (pintype "passive"))
    )
    (net (code "76") (name "unconnected-(RPI_ZERO-Pad16)") (class "Default")
      (node (ref "RPI_ZERO") (pin "16") (pinfunction "16_16") (pintype "passive"))
    )
    (net (code "77") (name "unconnected-(RPI_ZERO-Pad17)") (class "Default")
      (node (ref "RPI_ZERO") (pin "17") (pinfunction "17_17") (pintype "passive"))
    )
    (net (code "78") (name "unconnected-(RPI_ZERO-Pad18)") (class "Default")
      (node (ref "RPI_ZERO") (pin "18") (pinfunction "18_18") (pintype "passive"))
    )
    (net (code "79") (name "unconnected-(RPI_ZERO-Pad19)") (class "Default")
      (node (ref "RPI_ZERO") (pin "19") (pinfunction "19_19") (pintype "passive"))
    )
    (net (code "80") (name "unconnected-(RPI_ZERO-Pad21)") (class "Default")
      (node (ref "RPI_ZERO") (pin "21") (pinfunction "21_21") (pintype "passive"))
    )
    (net (code "81") (name "unconnected-(RPI_ZERO-Pad23)") (class "Default")
      (node (ref "RPI_ZERO") (pin "23") (pinfunction "23_23") (pintype "passive"))
    )
    (net (code "82") (name "unconnected-(RPI_ZERO-Pad25)") (class "Default")
      (node (ref "RPI_ZERO") (pin "25") (pinfunction "25_25") (pintype "passive"))
    )
    (net (code "83") (name "unconnected-(RPI_ZERO-Pad27)") (class "Default")
      (node (ref "RPI_ZERO") (pin "27") (pinfunction "27_27") (pintype "passive"))
    )
    (net (code "84") (name "unconnected-(RPI_ZERO-Pad29)") (class "Default")
      (node (ref "RPI_ZERO") (pin "29") (pinfunction "29_29") (pintype "passive"))
    )
    (net (code "85") (name "unconnected-(RPI_ZERO-Pad30)") (class "Default")
      (node (ref "RPI_ZERO") (pin "30") (pinfunction "30_30") (pintype "passive"))
    )
    (net (code "86") (name "unconnected-(RPI_ZERO-Pad33)") (class "Default")
      (node (ref "RPI_ZERO") (pin "33") (pinfunction "33_33") (pintype "passive"))
    )
    (net (code "87") (name "unconnected-(RPI_ZERO-Pad35)") (class "Default")
      (node (ref "RPI_ZERO") (pin "35") (pinfunction "35_35") (pintype "passive"))
    )
    (net (code "88") (name "unconnected-(RPI_ZERO-Pad37)") (class "Default")
      (node (ref "RPI_ZERO") (pin "37") (pinfunction "37_37") (pintype "passive"))
    )
    (net (code "89") (name "unconnected-(RPI_ZERO-Pad39)") (class "Default")
      (node (ref "RPI_ZERO") (pin "39") (pinfunction "39_39") (pintype "passive"))
    )
    (net (code "90") (name "unconnected-(STM32F103CB-PA1-Pad11)") (class "Default")
      (node (ref "STM32F103CB") (pin "11") (pinfunction "PA1_11") (pintype "bidirectional"))
    )
    (net (code "91") (name "unconnected-(STM32F103CB-PA8-Pad29)") (class "Default")
      (node (ref "STM32F103CB") (pin "29") (pinfunction "PA8_29") (pintype "bidirectional"))
    )
    (net (code "92") (name "unconnected-(STM32F103CB-PB4-Pad40)") (class "Default")
      (node (ref "STM32F103CB") (pin "40") (pinfunction "PB4_40") (pintype "bidirectional"))
    )
    (net (code "93") (name "unconnected-(STM32F103CB-PB5-Pad41)") (class "Default")
      (node (ref "STM32F103CB") (pin "41") (pinfunction "PB5_41") (pintype "bidirectional"))
    )
    (net (code "94") (name "unconnected-(STM32F103CB-PB8-Pad45)") (class "Default")
      (node (ref "STM32F103CB") (pin "45") (pinfunction "PB8_45") (pintype "bidirectional"))
    )
    (net (code "95") (name "unconnected-(STM32F103CB-PB9-Pad46)") (class "Default")
      (node (ref "STM32F103CB") (pin "46") (pinfunction "PB9_46") (pintype "bidirectional"))
    )
    (net (code "96") (name "unconnected-(STM32F103CB-PB10-Pad21)") (class "Default")
      (node (ref "STM32F103CB") (pin "21") (pinfunction "PB10_21") (pintype "bidirectional"))
    )
    (net (code "97") (name "unconnected-(STM32F103CB-PB11-Pad22)") (class "Default")
      (node (ref "STM32F103CB") (pin "22") (pinfunction "PB11_22") (pintype "bidirectional"))
    )
    (net (code "98") (name "unconnected-(STM32F103CB-PB13-Pad26)") (class "Default")
      (node (ref "STM32F103CB") (pin "26") (pinfunction "PB13_26") (pintype "bidirectional"))
    )
    (net (code "99") (name "unconnected-(STM32F103CB-PC14-OSC32_IN-Pad3)") (class "Default")
      (node (ref "STM32F103CB") (pin "3") (pinfunction "PC14-OSC32_IN_3") (pintype "bidirectional"))
    )
    (net (code "100") (name "unconnected-(STM32F103CB-PC15-OSC32_OUT-Pad4)") (class "Default")
      (node (ref "STM32F103CB") (pin "4") (pinfunction "PC15-OSC32_OUT_4") (pintype "bidirectional"))
    )
  )
)
